# main.net
KiCad netlist of a schematic drawn in EAGLE
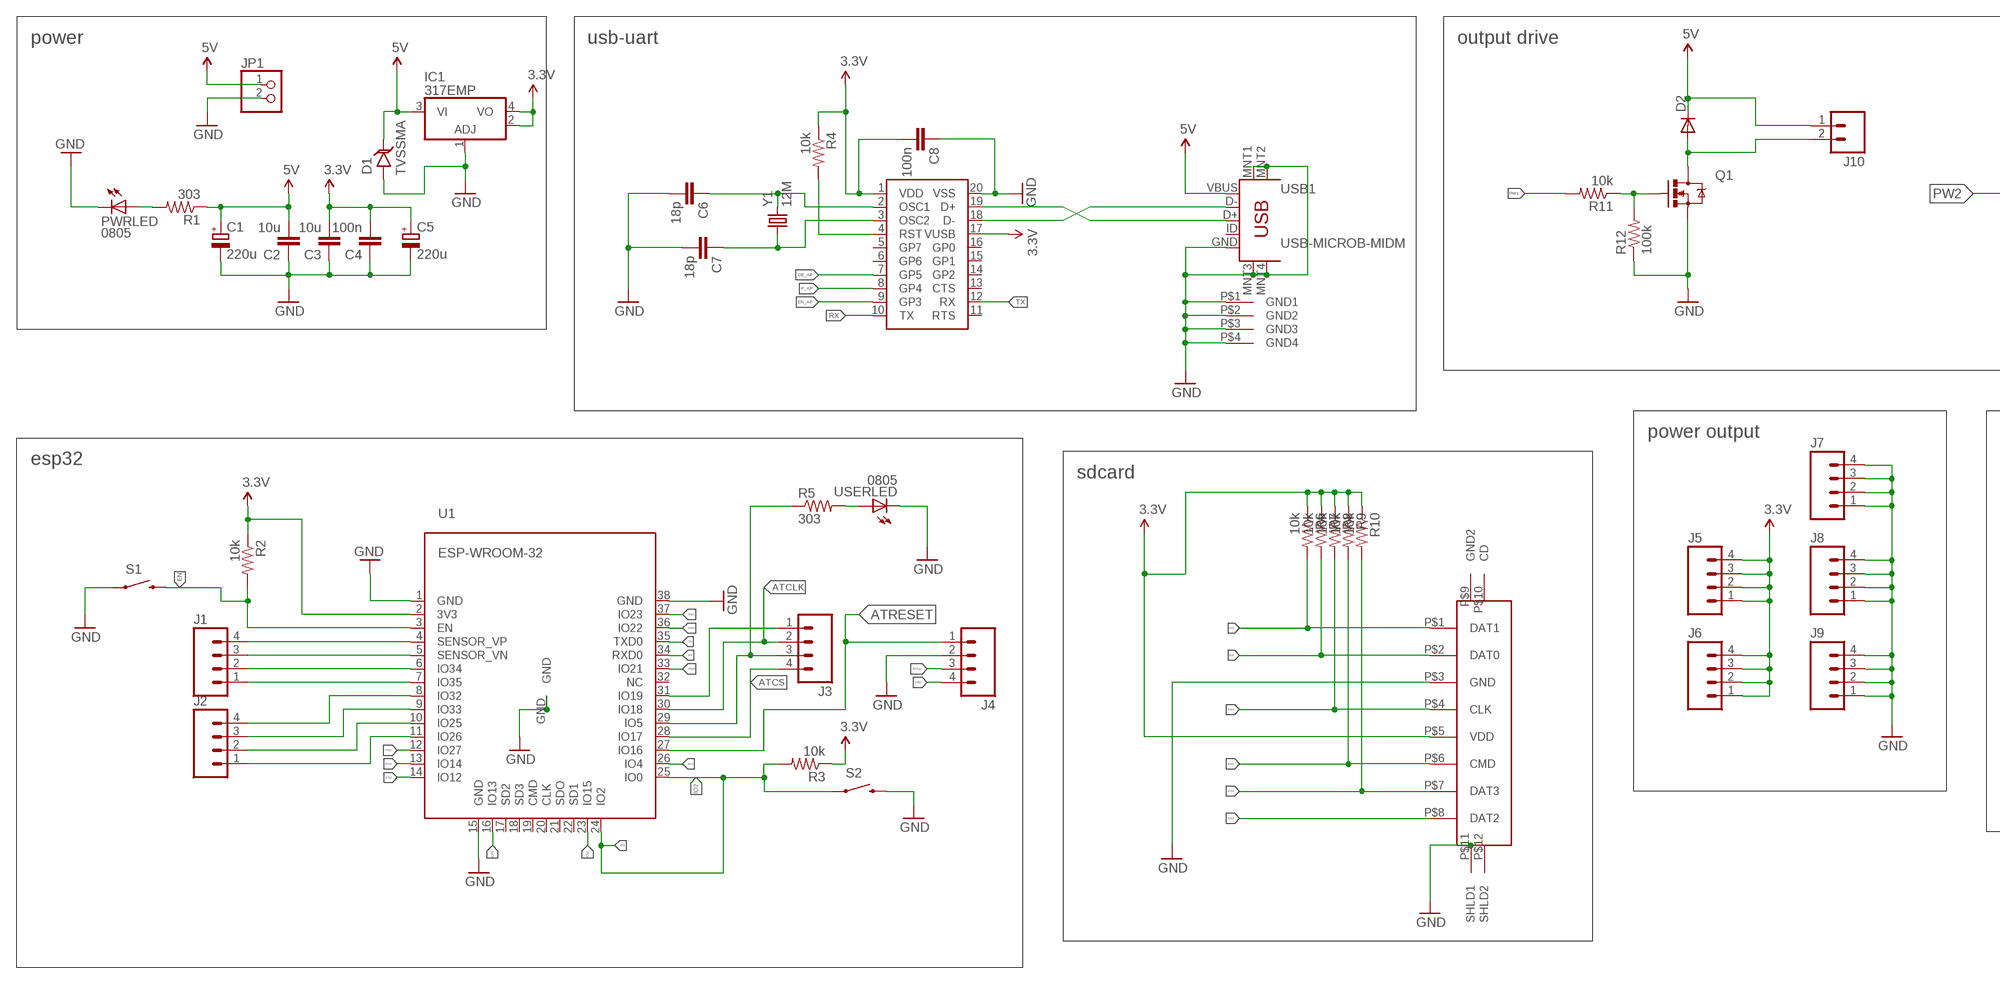
[diagram p0: schematic, sheet 1, part 1 of 2]
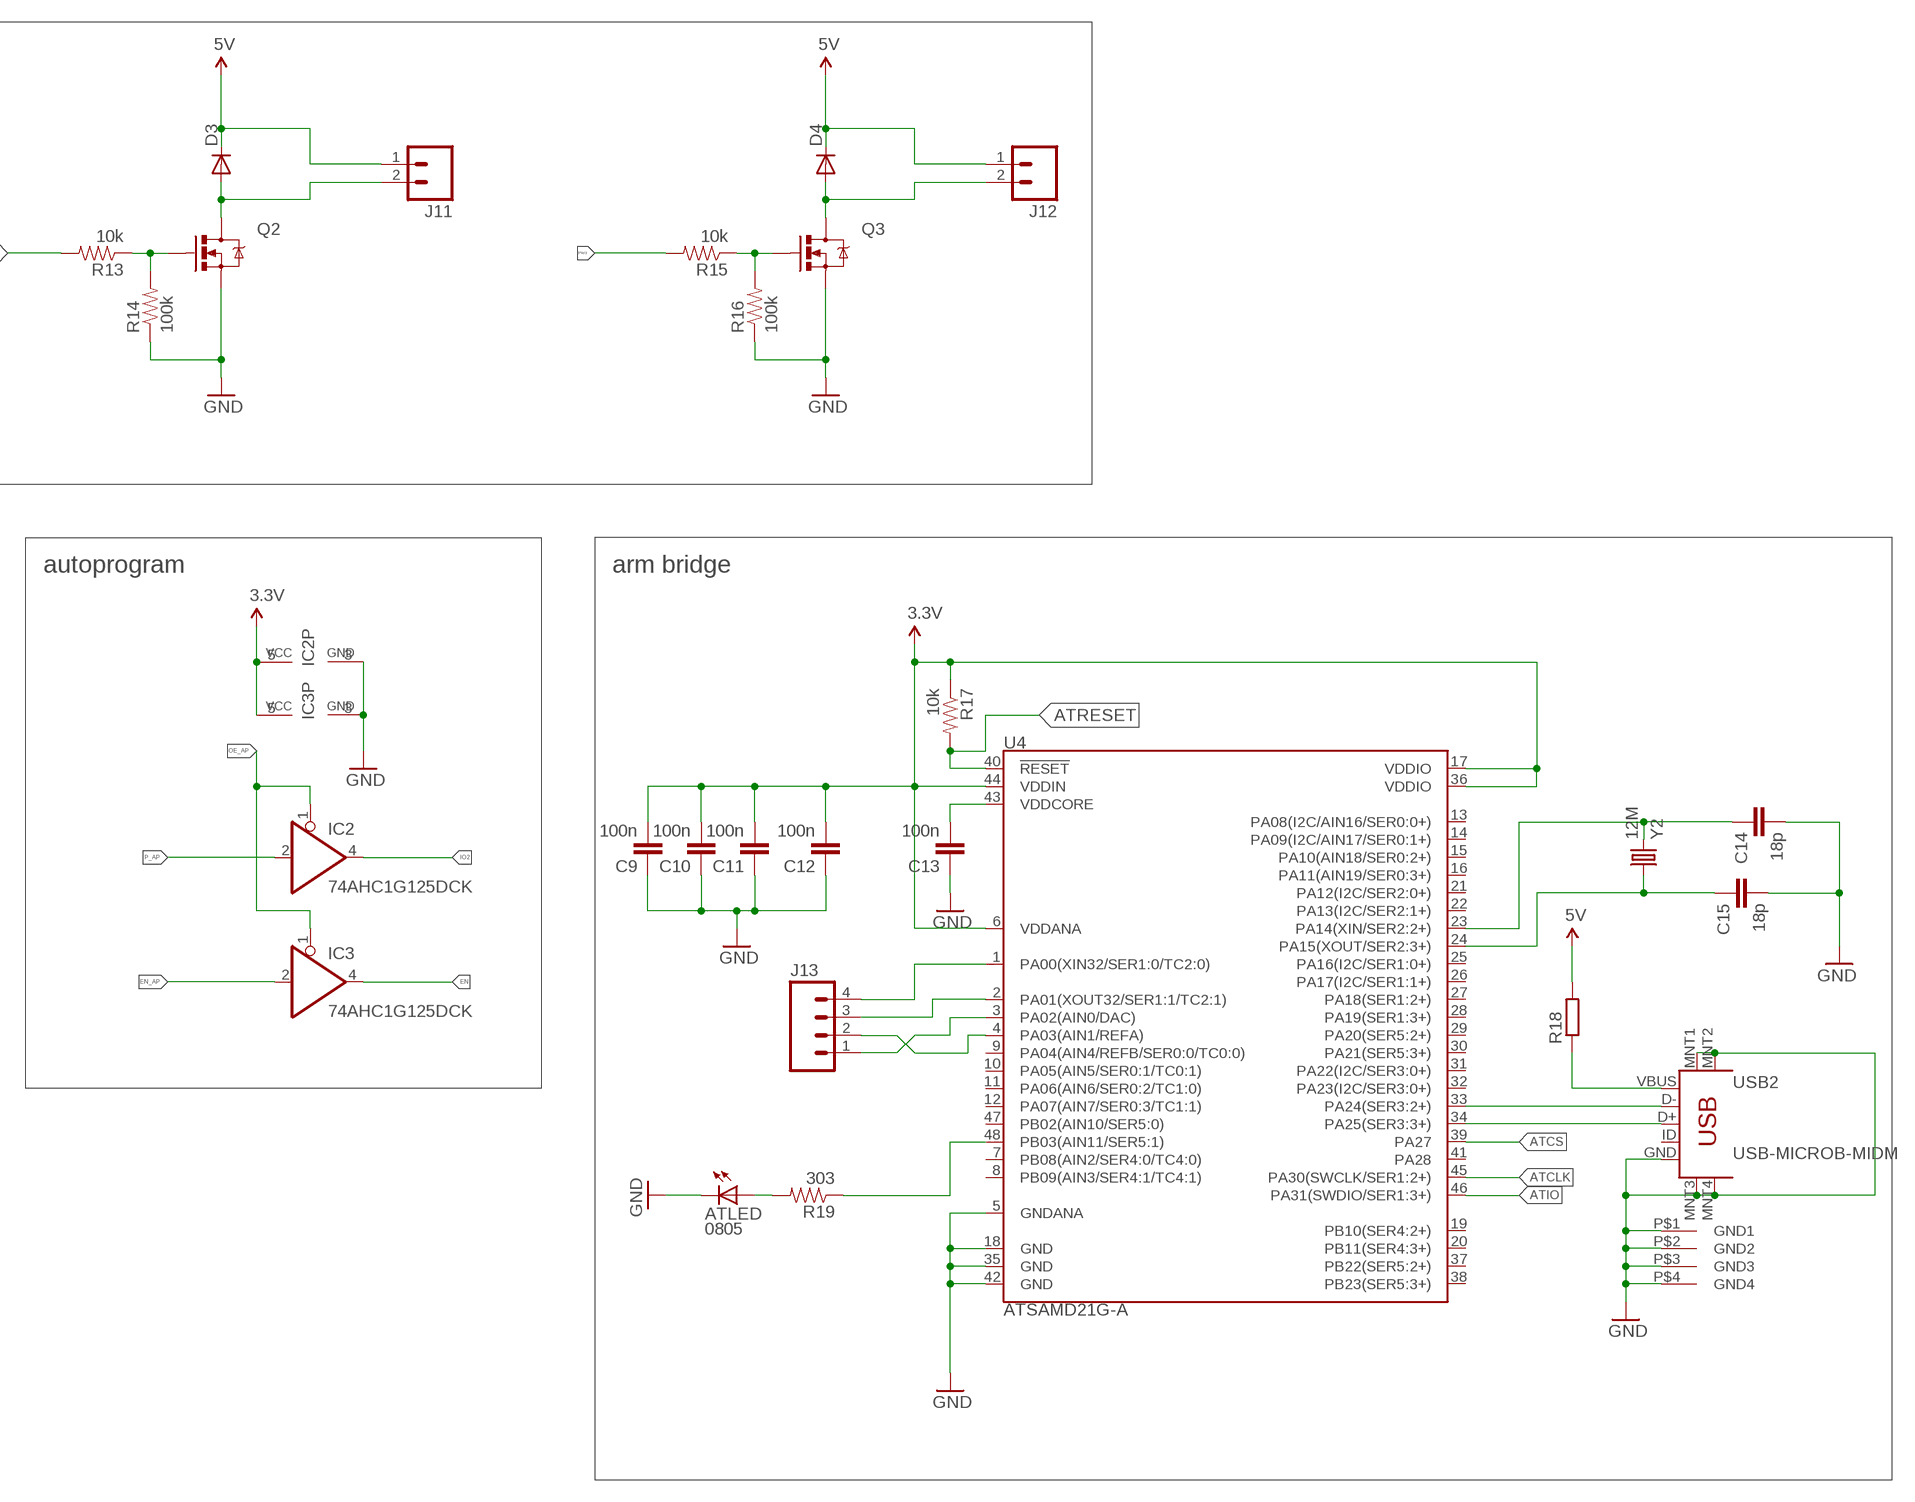
[diagram p1: schematic, sheet 1, part 2 of 2]

(export (version "E")
  (design (tool "Eeschema 10.0.6"))
  (components
    (comp (ref "ATLED")
      (value "0805")
      (footprint "eagle-import:SML0805")
      (libsource (lib "eagle-import") (part "LEDSML0805"))
    )
    (comp (ref "C1")
      (value "220u")
      (footprint "eagle-import:E2-4")
      (libsource (lib "eagle-import") (part "CPOL-EUE2-4"))
    )
    (comp (ref "C2")
      (value "10u")
      (footprint "eagle-import:0805")
      (libsource (lib "eagle-import") (part "CAP0805"))
    )
    (comp (ref "C3")
      (value "10u")
      (footprint "eagle-import:0805")
      (libsource (lib "eagle-import") (part "CAP0805"))
    )
    (comp (ref "C4")
      (value "100n")
      (footprint "eagle-import:0603-CAP")
      (libsource (lib "eagle-import") (part "CAP0603-CAP"))
    )
    (comp (ref "C5")
      (value "220u")
      (footprint "eagle-import:E2-4")
      (libsource (lib "eagle-import") (part "CPOL-EUE2-4"))
    )
    (comp (ref "C6")
      (value "18p")
      (footprint "eagle-import:0603-CAP")
      (libsource (lib "eagle-import") (part "CAP0603-CAP"))
    )
    (comp (ref "C7")
      (value "18p")
      (footprint "eagle-import:0603-CAP")
      (libsource (lib "eagle-import") (part "CAP0603-CAP"))
    )
    (comp (ref "C8")
      (value "100n")
      (footprint "eagle-import:0603-CAP")
      (libsource (lib "eagle-import") (part "CAP0603-CAP"))
    )
    (comp (ref "C9")
      (value "100n")
      (footprint "eagle-import:C0603K")
      (libsource (lib "eagle-import") (part "C-EUC0603K"))
    )
    (comp (ref "C10")
      (value "100n")
      (footprint "eagle-import:C0603K")
      (libsource (lib "eagle-import") (part "C-EUC0603K"))
    )
    (comp (ref "C11")
      (value "100n")
      (footprint "eagle-import:C0603K")
      (libsource (lib "eagle-import") (part "C-EUC0603K"))
    )
    (comp (ref "C12")
      (value "100n")
      (footprint "eagle-import:C0603K")
      (libsource (lib "eagle-import") (part "C-EUC0603K"))
    )
    (comp (ref "C13")
      (value "100n")
      (footprint "eagle-import:C0603K")
      (libsource (lib "eagle-import") (part "C-EUC0603K"))
    )
    (comp (ref "C14")
      (value "18p")
      (footprint "eagle-import:0603-CAP")
      (libsource (lib "eagle-import") (part "CAP0603-CAP"))
    )
    (comp (ref "C15")
      (value "18p")
      (footprint "eagle-import:0603-CAP")
      (libsource (lib "eagle-import") (part "CAP0603-CAP"))
    )
    (comp (ref "D1")
      (value "TVSSMA")
      (footprint "eagle-import:SMA-DIODE")
      (libsource (lib "eagle-import") (part "TVSSMA"))
    )
    (comp (ref "D2")
      (value "DIODE-SOD323-W")
      (footprint "eagle-import:SOD323-W")
      (libsource (lib "eagle-import") (part "DIODE-SOD323-W"))
    )
    (comp (ref "D3")
      (value "DIODE-SOD323-W")
      (footprint "eagle-import:SOD323-W")
      (libsource (lib "eagle-import") (part "DIODE-SOD323-W"))
    )
    (comp (ref "D4")
      (value "DIODE-SOD323-W")
      (footprint "eagle-import:SOD323-W")
      (libsource (lib "eagle-import") (part "DIODE-SOD323-W"))
    )
    (comp (ref "IC1")
      (value "317EMP")
      (footprint "eagle-import:SOT223")
      (libsource (lib "eagle-import") (part "317EMP"))
    )
    (comp (ref "IC2")
      (value "74AHC1G125DCK")
      (footprint "eagle-import:SC70-5")
      (libsource (lib "eagle-import") (part "741G125DCKAHC"))
    )
    (comp (ref "IC3")
      (value "74AHC1G125DCK")
      (footprint "eagle-import:SC70-5")
      (libsource (lib "eagle-import") (part "741G125DCKAHC"))
    )
    (comp (ref "J1")
      (value "M04LONGPADS")
      (footprint "eagle-import:1X04_LONGPADS")
      (libsource (lib "eagle-import") (part "M04LONGPADS"))
    )
    (comp (ref "J2")
      (value "M04LONGPADS")
      (footprint "eagle-import:1X04_LONGPADS")
      (libsource (lib "eagle-import") (part "M04LONGPADS"))
    )
    (comp (ref "J3")
      (value "M041.27MM")
      (footprint "eagle-import:1X04-1.27MM")
      (libsource (lib "eagle-import") (part "M041.27MM"))
    )
    (comp (ref "J4")
      (value "M041.27MM")
      (footprint "eagle-import:1X04-1.27MM")
      (libsource (lib "eagle-import") (part "M041.27MM"))
    )
    (comp (ref "J5")
      (value "M04LONGPADS")
      (footprint "eagle-import:1X04_LONGPADS")
      (libsource (lib "eagle-import") (part "M04LONGPADS"))
    )
    (comp (ref "J6")
      (value "M04LONGPADS")
      (footprint "eagle-import:1X04_LONGPADS")
      (libsource (lib "eagle-import") (part "M04LONGPADS"))
    )
    (comp (ref "J7")
      (value "M04LONGPADS")
      (footprint "eagle-import:1X04_LONGPADS")
      (libsource (lib "eagle-import") (part "M04LONGPADS"))
    )
    (comp (ref "J8")
      (value "M04LONGPADS")
      (footprint "eagle-import:1X04_LONGPADS")
      (libsource (lib "eagle-import") (part "M04LONGPADS"))
    )
    (comp (ref "J9")
      (value "M04LONGPADS")
      (footprint "eagle-import:1X04_LONGPADS")
      (libsource (lib "eagle-import") (part "M04LONGPADS"))
    )
    (comp (ref "J10")
      (value "M02LOCK_LONGPADS")
      (footprint "eagle-import:1X02_LOCK_LONGPADS")
      (libsource (lib "eagle-import") (part "M02LOCK_LONGPADS"))
    )
    (comp (ref "J11")
      (value "M02LOCK_LONGPADS")
      (footprint "eagle-import:1X02_LOCK_LONGPADS")
      (libsource (lib "eagle-import") (part "M02LOCK_LONGPADS"))
    )
    (comp (ref "J12")
      (value "M02LOCK_LONGPADS")
      (footprint "eagle-import:1X02_LOCK_LONGPADS")
      (libsource (lib "eagle-import") (part "M02LOCK_LONGPADS"))
    )
    (comp (ref "J13")
      (value "M041.27MM")
      (footprint "eagle-import:1X04-1.27MM")
      (libsource (lib "eagle-import") (part "M041.27MM"))
    )
    (comp (ref "JP1")
      (value "PINHD-1X2")
      (footprint "eagle-import:1X02")
      (libsource (lib "eagle-import") (part "PINHD-1X2"))
    )
    (comp (ref "PWRLED")
      (value "0805")
      (footprint "eagle-import:SML0805")
      (libsource (lib "eagle-import") (part "LEDSML0805"))
    )
    (comp (ref "Q1")
      (value "MOSFET-NCHANNELBSS138")
      (footprint "eagle-import:SOT23-3")
      (libsource (lib "eagle-import") (part "MOSFET-NCHANNELBSS138"))
    )
    (comp (ref "Q2")
      (value "MOSFET-NCHANNELBSS138")
      (footprint "eagle-import:SOT23-3")
      (libsource (lib "eagle-import") (part "MOSFET-NCHANNELBSS138"))
    )
    (comp (ref "Q3")
      (value "MOSFET-NCHANNELBSS138")
      (footprint "eagle-import:SOT23-3")
      (libsource (lib "eagle-import") (part "MOSFET-NCHANNELBSS138"))
    )
    (comp (ref "R1")
      (value "303")
      (footprint "eagle-import:0805")
      (libsource (lib "eagle-import") (part "RESISTOR0805-RES"))
    )
    (comp (ref "R2")
      (value "10k")
      (footprint "eagle-import:0805")
      (libsource (lib "eagle-import") (part "RESISTOR0805-RES"))
    )
    (comp (ref "R3")
      (value "10k")
      (footprint "eagle-import:0805")
      (libsource (lib "eagle-import") (part "RESISTOR0805-RES"))
    )
    (comp (ref "R4")
      (value "10k")
      (footprint "eagle-import:0805")
      (libsource (lib "eagle-import") (part "RESISTOR0805-RES"))
    )
    (comp (ref "R5")
      (value "303")
      (footprint "eagle-import:0805")
      (libsource (lib "eagle-import") (part "RESISTOR0805-RES"))
    )
    (comp (ref "R6")
      (value "10k")
      (footprint "eagle-import:0805")
      (libsource (lib "eagle-import") (part "RESISTOR0805-RES"))
    )
    (comp (ref "R7")
      (value "10k")
      (footprint "eagle-import:0805")
      (libsource (lib "eagle-import") (part "RESISTOR0805-RES"))
    )
    (comp (ref "R8")
      (value "10k")
      (footprint "eagle-import:0805")
      (libsource (lib "eagle-import") (part "RESISTOR0805-RES"))
    )
    (comp (ref "R9")
      (value "10k")
      (footprint "eagle-import:0805")
      (libsource (lib "eagle-import") (part "RESISTOR0805-RES"))
    )
    (comp (ref "R10")
      (value "10k")
      (footprint "eagle-import:0805")
      (libsource (lib "eagle-import") (part "RESISTOR0805-RES"))
    )
    (comp (ref "R11")
      (value "10k")
      (footprint "eagle-import:0805")
      (libsource (lib "eagle-import") (part "RESISTOR0805-RES"))
    )
    (comp (ref "R12")
      (value "100k")
      (footprint "eagle-import:0805")
      (libsource (lib "eagle-import") (part "RESISTOR0805-RES"))
    )
    (comp (ref "R13")
      (value "10k")
      (footprint "eagle-import:0805")
      (libsource (lib "eagle-import") (part "RESISTOR0805-RES"))
    )
    (comp (ref "R14")
      (value "100k")
      (footprint "eagle-import:0805")
      (libsource (lib "eagle-import") (part "RESISTOR0805-RES"))
    )
    (comp (ref "R15")
      (value "10k")
      (footprint "eagle-import:0805")
      (libsource (lib "eagle-import") (part "RESISTOR0805-RES"))
    )
    (comp (ref "R16")
      (value "100k")
      (footprint "eagle-import:0805")
      (libsource (lib "eagle-import") (part "RESISTOR0805-RES"))
    )
    (comp (ref "R17")
      (value "10k")
      (footprint "eagle-import:0805")
      (libsource (lib "eagle-import") (part "RESISTOR0805-RES"))
    )
    (comp (ref "R18")
      (value "R-EU_R2010W")
      (footprint "eagle-import:R2010W")
      (libsource (lib "eagle-import") (part "R-EU_R2010W"))
    )
    (comp (ref "R19")
      (value "303")
      (footprint "eagle-import:0805")
      (libsource (lib "eagle-import") (part "RESISTOR0805-RES"))
    )
    (comp (ref "S1")
      (value "SWITCH-MOMENTARY-2SMD")
      (footprint "eagle-import:TACTILE-SWITCH-SMD")
      (libsource (lib "eagle-import") (part "SWITCH-MOMENTARY-2SMD"))
    )
    (comp (ref "S2")
      (value "SWITCH-MOMENTARY-2SMD")
      (footprint "eagle-import:TACTILE-SWITCH-SMD")
      (libsource (lib "eagle-import") (part "SWITCH-MOMENTARY-2SMD"))
    )
    (comp (ref "U1")
      (value "ESP-WROOM-32")
      (footprint "eagle-import:ESP-WROOM-32")
      (libsource (lib "eagle-import") (part "ESP-WROOM-32"))
    )
    (comp (ref "U2")
      (value "MCP2200")
      (footprint "eagle-import:SO20W")
      (libsource (lib "eagle-import") (part "MCP2200"))
    )
    (comp (ref "U3")
      (value "MICROSD")
      (footprint "eagle-import:MICROSD")
      (libsource (lib "eagle-import") (part "MICROSD"))
    )
    (comp (ref "U4")
      (value "ATSAMD21G-A")
      (footprint "eagle-import:TQFP-48")
      (libsource (lib "eagle-import") (part "ATSAMD21G-A"))
    )
    (comp (ref "USB1")
      (value "USB-MICROB-MIDM")
      (footprint "eagle-import:USB-B-MICRO-MIDM")
      (libsource (lib "eagle-import") (part "USB-MICROB-MIDM"))
    )
    (comp (ref "USB2")
      (value "USB-MICROB-MIDM")
      (footprint "eagle-import:USB-B-MICRO-MIDM")
      (libsource (lib "eagle-import") (part "USB-MICROB-MIDM"))
    )
    (comp (ref "USERLED")
      (value "0805")
      (footprint "eagle-import:SML0805")
      (libsource (lib "eagle-import") (part "LEDSML0805"))
    )
    (comp (ref "Y1")
      (value "12M")
      (footprint "eagle-import:CRYSTAL-TXC-7A")
      (libsource (lib "eagle-import") (part "CRYSTALTXC-7A"))
    )
    (comp (ref "Y2")
      (value "12M")
      (footprint "eagle-import:CRYSTAL-TXC-7A")
      (libsource (lib "eagle-import") (part "CRYSTALTXC-7A"))
    )
  )
  (nets
    (net (code "1") (name "3.3V") (class "Default")
      (node (ref "C10") (pin "2") (pinfunction "2_2") (pintype "passive"))
      (node (ref "C11") (pin "2") (pinfunction "2_2") (pintype "passive"))
      (node (ref "C12") (pin "2") (pinfunction "2_2") (pintype "passive"))
      (node (ref "C3") (pin "2") (pinfunction "2_2") (pintype "passive"))
      (node (ref "C4") (pin "2") (pinfunction "2_2") (pintype "passive"))
      (node (ref "C5") (pin "+") (pinfunction "+_+") (pintype "passive"))
      (node (ref "C8") (pin "2") (pinfunction "2_2") (pintype "passive"))
      (node (ref "C9") (pin "2") (pinfunction "2_2") (pintype "passive"))
      (node (ref "IC1") (pin "2") (pinfunction "VO2_2") (pintype "passive"))
      (node (ref "IC1") (pin "4") (pinfunction "VO_4") (pintype "passive"))
      (node (ref "IC2") (pin "5") (pinfunction "VCC_5") (pintype "power_in"))
      (node (ref "IC3") (pin "5") (pinfunction "VCC_5") (pintype "power_in"))
      (node (ref "J5") (pin "1") (pinfunction "1_1") (pintype "passive"))
      (node (ref "J5") (pin "2") (pinfunction "2_2") (pintype "passive"))
      (node (ref "J5") (pin "3") (pinfunction "3_3") (pintype "passive"))
      (node (ref "J5") (pin "4") (pinfunction "4_4") (pintype "passive"))
      (node (ref "J6") (pin "1") (pinfunction "1_1") (pintype "passive"))
      (node (ref "J6") (pin "2") (pinfunction "2_2") (pintype "passive"))
      (node (ref "J6") (pin "3") (pinfunction "3_3") (pintype "passive"))
      (node (ref "J6") (pin "4") (pinfunction "4_4") (pintype "passive"))
      (node (ref "R10") (pin "1") (pinfunction "1_1") (pintype "passive"))
      (node (ref "R17") (pin "1") (pinfunction "1_1") (pintype "passive"))
      (node (ref "R2") (pin "1") (pinfunction "1_1") (pintype "passive"))
      (node (ref "R3") (pin "1") (pinfunction "1_1") (pintype "passive"))
      (node (ref "R4") (pin "1") (pinfunction "1_1") (pintype "passive"))
      (node (ref "R6") (pin "1") (pinfunction "1_1") (pintype "passive"))
      (node (ref "R7") (pin "1") (pinfunction "1_1") (pintype "passive"))
      (node (ref "R8") (pin "1") (pinfunction "1_1") (pintype "passive"))
      (node (ref "R9") (pin "1") (pinfunction "1_1") (pintype "passive"))
      (node (ref "U1") (pin "2") (pinfunction "3V3_2") (pintype "bidirectional"))
      (node (ref "U2") (pin "1") (pinfunction "VDD_1") (pintype "bidirectional"))
      (node (ref "U2") (pin "17") (pinfunction "VUSB_17") (pintype "bidirectional"))
      (node (ref "U3") (pin "P$5") (pinfunction "VDD_P$5") (pintype "bidirectional"))
      (node (ref "U4") (pin "17") (pinfunction "VDDIO_17") (pintype "bidirectional"))
      (node (ref "U4") (pin "36") (pinfunction "VDDIO_36") (pintype "bidirectional"))
      (node (ref "U4") (pin "44") (pinfunction "VDDIN_44") (pintype "bidirectional"))
      (node (ref "U4") (pin "6") (pinfunction "VDDANA_6") (pintype "bidirectional"))
    )
    (net (code "2") (name "5V") (class "Default")
      (node (ref "C1") (pin "+") (pinfunction "+_+") (pintype "passive"))
      (node (ref "C2") (pin "2") (pinfunction "2_2") (pintype "passive"))
      (node (ref "D1") (pin "C") (pinfunction "C_C") (pintype "passive"))
      (node (ref "D2") (pin "C") (pinfunction "C_C") (pintype "passive"))
      (node (ref "D3") (pin "C") (pinfunction "C_C") (pintype "passive"))
      (node (ref "D4") (pin "C") (pinfunction "C_C") (pintype "passive"))
      (node (ref "IC1") (pin "3") (pinfunction "VI_3") (pintype "input"))
      (node (ref "J10") (pin "1") (pinfunction "1_1") (pintype "passive"))
      (node (ref "J11") (pin "1") (pinfunction "1_1") (pintype "passive"))
      (node (ref "J12") (pin "1") (pinfunction "1_1") (pintype "passive"))
      (node (ref "JP1") (pin "1") (pinfunction "1_1") (pintype "passive"))
      (node (ref "R1") (pin "1") (pinfunction "1_1") (pintype "passive"))
      (node (ref "R18") (pin "2") (pinfunction "2_2") (pintype "passive"))
      (node (ref "USB1") (pin "VBUS") (pinfunction "VBUS_VBUS") (pintype "bidirectional"))
    )
    (net (code "3") (name "ATCLK") (class "Default")
      (node (ref "J3") (pin "2") (pinfunction "2_2") (pintype "passive"))
      (node (ref "J4") (pin "3") (pinfunction "3_3") (pintype "passive"))
      (node (ref "U1") (pin "30") (pinfunction "IO18_30") (pintype "bidirectional"))
      (node (ref "U4") (pin "45") (pinfunction "PA30(SWCLK/SER1:2+)_45") (pintype "bidirectional"))
    )
    (net (code "4") (name "ATCS") (class "Default")
      (node (ref "J3") (pin "4") (pinfunction "4_4") (pintype "passive"))
      (node (ref "U1") (pin "28") (pinfunction "IO17_28") (pintype "bidirectional"))
      (node (ref "U4") (pin "39") (pinfunction "PA27_39") (pintype "bidirectional"))
    )
    (net (code "5") (name "ATIO") (class "Default")
      (node (ref "J4") (pin "4") (pinfunction "4_4") (pintype "passive"))
      (node (ref "U1") (pin "12") (pinfunction "IO27_12") (pintype "bidirectional"))
      (node (ref "U4") (pin "46") (pinfunction "PA31(SWDIO/SER1:3+)_46") (pintype "bidirectional"))
    )
    (net (code "6") (name "ATRESET") (class "Default")
      (node (ref "J4") (pin "1") (pinfunction "1_1") (pintype "passive"))
      (node (ref "R17") (pin "2") (pinfunction "2_2") (pintype "passive"))
      (node (ref "U1") (pin "27") (pinfunction "IO16_27") (pintype "bidirectional"))
      (node (ref "U4") (pin "40") (pinfunction "~{RESET}_40") (pintype "bidirectional"))
    )
    (net (code "7") (name "EN") (class "Default")
      (node (ref "IC3") (pin "4") (pinfunction "O_4") (pintype "tri_state"))
      (node (ref "R2") (pin "2") (pinfunction "2_2") (pintype "passive"))
      (node (ref "S1") (pin "3") (pinfunction "2_3") (pintype "passive"))
      (node (ref "U1") (pin "3") (pinfunction "EN_3") (pintype "bidirectional"))
    )
    (net (code "8") (name "EN_AP") (class "Default")
      (node (ref "IC3") (pin "2") (pinfunction "I_2") (pintype "input"))
      (node (ref "U2") (pin "9") (pinfunction "GP3_9") (pintype "bidirectional"))
    )
    (net (code "9") (name "GND") (class "Default")
      (node (ref "ATLED") (pin "C") (pinfunction "C_C") (pintype "passive"))
      (node (ref "C1") (pin "-") (pinfunction "-_-") (pintype "passive"))
      (node (ref "C10") (pin "1") (pinfunction "1_1") (pintype "passive"))
      (node (ref "C11") (pin "1") (pinfunction "1_1") (pintype "passive"))
      (node (ref "C12") (pin "1") (pinfunction "1_1") (pintype "passive"))
      (node (ref "C13") (pin "1") (pinfunction "1_1") (pintype "passive"))
      (node (ref "C14") (pin "2") (pinfunction "2_2") (pintype "passive"))
      (node (ref "C15") (pin "2") (pinfunction "2_2") (pintype "passive"))
      (node (ref "C2") (pin "1") (pinfunction "1_1") (pintype "passive"))
      (node (ref "C3") (pin "1") (pinfunction "1_1") (pintype "passive"))
      (node (ref "C4") (pin "1") (pinfunction "1_1") (pintype "passive"))
      (node (ref "C5") (pin "-") (pinfunction "-_-") (pintype "passive"))
      (node (ref "C6") (pin "2") (pinfunction "2_2") (pintype "passive"))
      (node (ref "C7") (pin "2") (pinfunction "2_2") (pintype "passive"))
      (node (ref "C8") (pin "1") (pinfunction "1_1") (pintype "passive"))
      (node (ref "C9") (pin "1") (pinfunction "1_1") (pintype "passive"))
      (node (ref "D1") (pin "A") (pinfunction "A_A") (pintype "passive"))
      (node (ref "IC1") (pin "1") (pinfunction "ADJ_1") (pintype "input"))
      (node (ref "IC2") (pin "3") (pinfunction "GND_3") (pintype "power_in"))
      (node (ref "IC3") (pin "3") (pinfunction "GND_3") (pintype "power_in"))
      (node (ref "J4") (pin "2") (pinfunction "2_2") (pintype "passive"))
      (node (ref "J7") (pin "1") (pinfunction "1_1") (pintype "passive"))
      (node (ref "J7") (pin "2") (pinfunction "2_2") (pintype "passive"))
      (node (ref "J7") (pin "3") (pinfunction "3_3") (pintype "passive"))
      (node (ref "J7") (pin "4") (pinfunction "4_4") (pintype "passive"))
      (node (ref "J8") (pin "1") (pinfunction "1_1") (pintype "passive"))
      (node (ref "J8") (pin "2") (pinfunction "2_2") (pintype "passive"))
      (node (ref "J8") (pin "3") (pinfunction "3_3") (pintype "passive"))
      (node (ref "J8") (pin "4") (pinfunction "4_4") (pintype "passive"))
      (node (ref "J9") (pin "1") (pinfunction "1_1") (pintype "passive"))
      (node (ref "J9") (pin "2") (pinfunction "2_2") (pintype "passive"))
      (node (ref "J9") (pin "3") (pinfunction "3_3") (pintype "passive"))
      (node (ref "J9") (pin "4") (pinfunction "4_4") (pintype "passive"))
      (node (ref "JP1") (pin "2") (pinfunction "2_2") (pintype "passive"))
      (node (ref "PWRLED") (pin "C") (pinfunction "C_C") (pintype "passive"))
      (node (ref "Q1") (pin "2") (pinfunction "S_2") (pintype "passive"))
      (node (ref "Q2") (pin "2") (pinfunction "S_2") (pintype "passive"))
      (node (ref "Q3") (pin "2") (pinfunction "S_2") (pintype "passive"))
      (node (ref "R12") (pin "1") (pinfunction "1_1") (pintype "passive"))
      (node (ref "R14") (pin "1") (pinfunction "1_1") (pintype "passive"))
      (node (ref "R16") (pin "1") (pinfunction "1_1") (pintype "passive"))
      (node (ref "S1") (pin "1") (pinfunction "1_1") (pintype "passive"))
      (node (ref "S2") (pin "3") (pinfunction "2_3") (pintype "passive"))
      (node (ref "U1") (pin "1") (pinfunction "GND_1") (pintype "bidirectional"))
      (node (ref "U1") (pin "15") (pinfunction "GND_15") (pintype "bidirectional"))
      (node (ref "U1") (pin "38") (pinfunction "GND_38") (pintype "bidirectional"))
      (node (ref "U1") (pin "GND") (pinfunction "GND_GND") (pintype "bidirectional"))
      (node (ref "U2") (pin "20") (pinfunction "VSS_20") (pintype "bidirectional"))
      (node (ref "U3") (pin "P$11") (pinfunction "SHLD1_P$11") (pintype "bidirectional"))
      (node (ref "U3") (pin "P$12") (pinfunction "SHLD2_P$12") (pintype "bidirectional"))
      (node (ref "U3") (pin "P$3") (pinfunction "GND_P$3") (pintype "bidirectional"))
      (node (ref "U4") (pin "18") (pinfunction "GND_18") (pintype "bidirectional"))
      (node (ref "U4") (pin "35") (pinfunction "GND_35") (pintype "bidirectional"))
      (node (ref "U4") (pin "42") (pinfunction "GND_42") (pintype "bidirectional"))
      (node (ref "U4") (pin "5") (pinfunction "GNDANA_5") (pintype "bidirectional"))
      (node (ref "USB1") (pin "GND") (pinfunction "GND_GND") (pintype "bidirectional"))
      (node (ref "USB1") (pin "MNT1") (pinfunction "MTN1_MNT1") (pintype "bidirectional"))
      (node (ref "USB1") (pin "MNT2") (pinfunction "MTN2_MNT2") (pintype "bidirectional"))
      (node (ref "USB1") (pin "MNT3") (pinfunction "MTN3_MNT3") (pintype "bidirectional"))
      (node (ref "USB1") (pin "MNT4") (pinfunction "MTN4_MNT4") (pintype "bidirectional"))
      (node (ref "USB1") (pin "P$1") (pinfunction "GND1_P$1") (pintype "bidirectional"))
      (node (ref "USB1") (pin "P$2") (pinfunction "GND2_P$2") (pintype "bidirectional"))
      (node (ref "USB1") (pin "P$3") (pinfunction "GND3_P$3") (pintype "bidirectional"))
      (node (ref "USB1") (pin "P$4") (pinfunction "GND4_P$4") (pintype "bidirectional"))
      (node (ref "USB2") (pin "GND") (pinfunction "GND_GND") (pintype "bidirectional"))
      (node (ref "USB2") (pin "MNT1") (pinfunction "MTN1_MNT1") (pintype "bidirectional"))
      (node (ref "USB2") (pin "MNT2") (pinfunction "MTN2_MNT2") (pintype "bidirectional"))
      (node (ref "USB2") (pin "MNT3") (pinfunction "MTN3_MNT3") (pintype "bidirectional"))
      (node (ref "USB2") (pin "MNT4") (pinfunction "MTN4_MNT4") (pintype "bidirectional"))
      (node (ref "USB2") (pin "P$1") (pinfunction "GND1_P$1") (pintype "bidirectional"))
      (node (ref "USB2") (pin "P$2") (pinfunction "GND2_P$2") (pintype "bidirectional"))
      (node (ref "USB2") (pin "P$3") (pinfunction "GND3_P$3") (pintype "bidirectional"))
      (node (ref "USB2") (pin "P$4") (pinfunction "GND4_P$4") (pintype "bidirectional"))
      (node (ref "USERLED") (pin "C") (pinfunction "C_C") (pintype "passive"))
    )
    (net (code "10") (name "IO2") (class "Default")
      (node (ref "IC2") (pin "4") (pinfunction "O_4") (pintype "tri_state"))
      (node (ref "R3") (pin "2") (pinfunction "2_2") (pintype "passive"))
      (node (ref "R7") (pin "2") (pinfunction "2_2") (pintype "passive"))
      (node (ref "S2") (pin "1") (pinfunction "1_1") (pintype "passive"))
      (node (ref "U1") (pin "24") (pinfunction "IO2_24") (pintype "bidirectional"))
      (node (ref "U1") (pin "25") (pinfunction "IO0_25") (pintype "bidirectional"))
      (node (ref "U3") (pin "P$2") (pinfunction "DAT0_P$2") (pintype "bidirectional"))
    )
    (net (code "11") (name "IO4") (class "Default")
      (node (ref "R6") (pin "2") (pinfunction "2_2") (pintype "passive"))
      (node (ref "U1") (pin "26") (pinfunction "IO4_26") (pintype "bidirectional"))
      (node (ref "U3") (pin "P$1") (pinfunction "DAT1_P$1") (pintype "bidirectional"))
    )
    (net (code "12") (name "IO12") (class "Default")
      (node (ref "U1") (pin "14") (pinfunction "IO12_14") (pintype "bidirectional"))
      (node (ref "U3") (pin "P$8") (pinfunction "DAT2_P$8") (pintype "bidirectional"))
    )
    (net (code "13") (name "IO13") (class "Default")
      (node (ref "R10") (pin "2") (pinfunction "2_2") (pintype "passive"))
      (node (ref "U1") (pin "16") (pinfunction "IO13_16") (pintype "bidirectional"))
      (node (ref "U3") (pin "P$7") (pinfunction "DAT3_P$7") (pintype "bidirectional"))
    )
    (net (code "14") (name "IO14") (class "Default")
      (node (ref "R8") (pin "2") (pinfunction "2_2") (pintype "passive"))
      (node (ref "U1") (pin "13") (pinfunction "IO14_13") (pintype "bidirectional"))
      (node (ref "U3") (pin "P$4") (pinfunction "CLK_P$4") (pintype "bidirectional"))
    )
    (net (code "15") (name "IO15") (class "Default")
      (node (ref "R9") (pin "2") (pinfunction "2_2") (pintype "passive"))
      (node (ref "U1") (pin "23") (pinfunction "IO15_23") (pintype "bidirectional"))
      (node (ref "U3") (pin "P$6") (pinfunction "CMD_P$6") (pintype "bidirectional"))
    )
    (net (code "16") (name "Net-(ATLED-PadA)") (class "Default")
      (node (ref "ATLED") (pin "A") (pinfunction "A_A") (pintype "passive"))
      (node (ref "R19") (pin "2") (pinfunction "2_2") (pintype "passive"))
    )
    (net (code "17") (name "Net-(PWRLED-PadA)") (class "Default")
      (node (ref "PWRLED") (pin "A") (pinfunction "A_A") (pintype "passive"))
      (node (ref "R1") (pin "2") (pinfunction "2_2") (pintype "passive"))
    )
    (net (code "18") (name "Net-(Q1-D)") (class "Default")
      (node (ref "D2") (pin "A") (pinfunction "A_A") (pintype "passive"))
      (node (ref "J10") (pin "2") (pinfunction "2_2") (pintype "passive"))
      (node (ref "Q1") (pin "3") (pinfunction "D_3") (pintype "passive"))
    )
    (net (code "19") (name "Net-(Q1-G)") (class "Default")
      (node (ref "Q1") (pin "1") (pinfunction "G_1") (pintype "passive"))
      (node (ref "R11") (pin "1") (pinfunction "1_1") (pintype "passive"))
      (node (ref "R12") (pin "2") (pinfunction "2_2") (pintype "passive"))
    )
    (net (code "20") (name "Net-(Q2-D)") (class "Default")
      (node (ref "D3") (pin "A") (pinfunction "A_A") (pintype "passive"))
      (node (ref "J11") (pin "2") (pinfunction "2_2") (pintype "passive"))
      (node (ref "Q2") (pin "3") (pinfunction "D_3") (pintype "passive"))
    )
    (net (code "21") (name "Net-(Q2-G)") (class "Default")
      (node (ref "Q2") (pin "1") (pinfunction "G_1") (pintype "passive"))
      (node (ref "R13") (pin "1") (pinfunction "1_1") (pintype "passive"))
      (node (ref "R14") (pin "2") (pinfunction "2_2") (pintype "passive"))
    )
    (net (code "22") (name "Net-(Q3-D)") (class "Default")
      (node (ref "D4") (pin "A") (pinfunction "A_A") (pintype "passive"))
      (node (ref "J12") (pin "2") (pinfunction "2_2") (pintype "passive"))
      (node (ref "Q3") (pin "3") (pinfunction "D_3") (pintype "passive"))
    )
    (net (code "23") (name "Net-(Q3-G)") (class "Default")
      (node (ref "Q3") (pin "1") (pinfunction "G_1") (pintype "passive"))
      (node (ref "R15") (pin "1") (pinfunction "1_1") (pintype "passive"))
      (node (ref "R16") (pin "2") (pinfunction "2_2") (pintype "passive"))
    )
    (net (code "24") (name "Net-(R5-Pad2)") (class "Default")
      (node (ref "R5") (pin "2") (pinfunction "2_2") (pintype "passive"))
      (node (ref "USERLED") (pin "A") (pinfunction "A_A") (pintype "passive"))
    )
    (net (code "25") (name "Net-(R18-Pad1)") (class "Default")
      (node (ref "R18") (pin "1") (pinfunction "1_1") (pintype "passive"))
      (node (ref "USB2") (pin "VBUS") (pinfunction "VBUS_VBUS") (pintype "bidirectional"))
    )
    (net (code "26") (name "Net-(U1-IO5)") (class "Default")
      (node (ref "J3") (pin "3") (pinfunction "3_3") (pintype "passive"))
      (node (ref "R5") (pin "1") (pinfunction "1_1") (pintype "passive"))
      (node (ref "U1") (pin "29") (pinfunction "IO5_29") (pintype "bidirectional"))
    )
    (net (code "27") (name "Net-(U1-IO19)") (class "Default")
      (node (ref "J3") (pin "1") (pinfunction "1_1") (pintype "passive"))
      (node (ref "U1") (pin "31") (pinfunction "IO19_31") (pintype "bidirectional"))
    )
    (net (code "28") (name "Net-(U1-IO25)") (class "Default")
      (node (ref "J2") (pin "2") (pinfunction "2_2") (pintype "passive"))
      (node (ref "U1") (pin "10") (pinfunction "IO25_10") (pintype "bidirectional"))
    )
    (net (code "29") (name "Net-(U1-IO26)") (class "Default")
      (node (ref "J2") (pin "1") (pinfunction "1_1") (pintype "passive"))
      (node (ref "U1") (pin "11") (pinfunction "IO26_11") (pintype "bidirectional"))
    )
    (net (code "30") (name "Net-(U1-IO32)") (class "Default")
      (node (ref "J2") (pin "4") (pinfunction "4_4") (pintype "passive"))
      (node (ref "U1") (pin "8") (pinfunction "IO32_8") (pintype "bidirectional"))
    )
    (net (code "31") (name "Net-(U1-IO33)") (class "Default")
      (node (ref "J2") (pin "3") (pinfunction "3_3") (pintype "passive"))
      (node (ref "U1") (pin "9") (pinfunction "IO33_9") (pintype "bidirectional"))
    )
    (net (code "32") (name "Net-(U1-IO34)") (class "Default")
      (node (ref "J1") (pin "2") (pinfunction "2_2") (pintype "passive"))
      (node (ref "U1") (pin "6") (pinfunction "IO34_6") (pintype "bidirectional"))
    )
    (net (code "33") (name "Net-(U1-IO35)") (class "Default")
      (node (ref "J1") (pin "1") (pinfunction "1_1") (pintype "passive"))
      (node (ref "U1") (pin "7") (pinfunction "IO35_7") (pintype "bidirectional"))
    )
    (net (code "34") (name "Net-(U1-SENSOR_VN)") (class "Default")
      (node (ref "J1") (pin "3") (pinfunction "3_3") (pintype "passive"))
      (node (ref "U1") (pin "5") (pinfunction "SENSOR_VN_5") (pintype "bidirectional"))
    )
    (net (code "35") (name "Net-(U1-SENSOR_VP)") (class "Default")
      (node (ref "J1") (pin "4") (pinfunction "4_4") (pintype "passive"))
      (node (ref "U1") (pin "4") (pinfunction "SENSOR_VP_4") (pintype "bidirectional"))
    )
    (net (code "36") (name "Net-(U2-D+)") (class "Default")
      (node (ref "U2") (pin "19") (pinfunction "D+_19") (pintype "bidirectional"))
      (node (ref "USB1") (pin "D+") (pinfunction "D+_D+") (pintype "bidirectional"))
    )
    (net (code "37") (name "Net-(U2-D-)") (class "Default")
      (node (ref "U2") (pin "18") (pinfunction "D-_18") (pintype "bidirectional"))
      (node (ref "USB1") (pin "D-") (pinfunction "D-_D-") (pintype "bidirectional"))
    )
    (net (code "38") (name "Net-(U2-OSC1)") (class "Default")
      (node (ref "C6") (pin "1") (pinfunction "1_1") (pintype "passive"))
      (node (ref "U2") (pin "2") (pinfunction "OSC1_2") (pintype "bidirectional"))
      (node (ref "Y1") (pin "P$2") (pinfunction "2_P$2") (pintype "passive"))
    )
    (net (code "39") (name "Net-(U2-OSC2)") (class "Default")
      (node (ref "C7") (pin "1") (pinfunction "1_1") (pintype "passive"))
      (node (ref "U2") (pin "3") (pinfunction "OSC2_3") (pintype "bidirectional"))
      (node (ref "Y1") (pin "P$1") (pinfunction "1_P$1") (pintype "passive"))
    )
    (net (code "40") (name "Net-(U2-RST)") (class "Default")
      (node (ref "R4") (pin "2") (pinfunction "2_2") (pintype "passive"))
      (node (ref "U2") (pin "4") (pinfunction "RST_4") (pintype "bidirectional"))
    )
    (net (code "41") (name "Net-(U4-PA00(XIN32{slash}SER1:0{slash}TC2:0))") (class "Default")
      (node (ref "J13") (pin "4") (pinfunction "4_4") (pintype "passive"))
      (node (ref "U4") (pin "1") (pinfunction "PA00(XIN32/SER1:0/TC2:0)_1") (pintype "bidirectional"))
    )
    (net (code "42") (name "Net-(U4-PA01(XOUT32{slash}SER1:1{slash}TC2:1))") (class "Default")
      (node (ref "J13") (pin "3") (pinfunction "3_3") (pintype "passive"))
      (node (ref "U4") (pin "2") (pinfunction "PA01(XOUT32/SER1:1/TC2:1)_2") (pintype "bidirectional"))
    )
    (net (code "43") (name "Net-(U4-PA02(AIN0{slash}DAC))") (class "Default")
      (node (ref "J13") (pin "1") (pinfunction "1_1") (pintype "passive"))
      (node (ref "U4") (pin "3") (pinfunction "PA02(AIN0/DAC)_3") (pintype "bidirectional"))
    )
    (net (code "44") (name "Net-(U4-PA03(AIN1{slash}REFA))") (class "Default")
      (node (ref "J13") (pin "2") (pinfunction "2_2") (pintype "passive"))
      (node (ref "U4") (pin "4") (pinfunction "PA03(AIN1/REFA)_4") (pintype "bidirectional"))
    )
    (net (code "45") (name "Net-(U4-PA14(XIN{slash}SER2:2+))") (class "Default")
      (node (ref "C14") (pin "1") (pinfunction "1_1") (pintype "passive"))
      (node (ref "U4") (pin "23") (pinfunction "PA14(XIN/SER2:2+)_23") (pintype "bidirectional"))
      (node (ref "Y2") (pin "P$2") (pinfunction "2_P$2") (pintype "passive"))
    )
    (net (code "46") (name "Net-(U4-PA15(XOUT{slash}SER2:3+))") (class "Default")
      (node (ref "C15") (pin "1") (pinfunction "1_1") (pintype "passive"))
      (node (ref "U4") (pin "24") (pinfunction "PA15(XOUT/SER2:3+)_24") (pintype "bidirectional"))
      (node (ref "Y2") (pin "P$1") (pinfunction "1_P$1") (pintype "passive"))
    )
    (net (code "47") (name "Net-(U4-PA24(SER3:2+))") (class "Default")
      (node (ref "U4") (pin "33") (pinfunction "PA24(SER3:2+)_33") (pintype "bidirectional"))
      (node (ref "USB2") (pin "D-") (pinfunction "D-_D-") (pintype "bidirectional"))
    )
    (net (code "48") (name "Net-(U4-PA25(SER3:3+))") (class "Default")
      (node (ref "U4") (pin "34") (pinfunction "PA25(SER3:3+)_34") (pintype "bidirectional"))
      (node (ref "USB2") (pin "D+") (pinfunction "D+_D+") (pintype "bidirectional"))
    )
    (net (code "49") (name "Net-(U4-PB03(AIN11{slash}SER5:1))") (class "Default")
      (node (ref "R19") (pin "1") (pinfunction "1_1") (pintype "passive"))
      (node (ref "U4") (pin "48") (pinfunction "PB03(AIN11/SER5:1)_48") (pintype "bidirectional"))
    )
    (net (code "50") (name "Net-(U4-VDDCORE)") (class "Default")
      (node (ref "C13") (pin "2") (pinfunction "2_2") (pintype "passive"))
      (node (ref "U4") (pin "43") (pinfunction "VDDCORE_43") (pintype "bidirectional"))
    )
    (net (code "51") (name "OE_AP") (class "Default")
      (node (ref "IC2") (pin "1") (pinfunction "OE_1") (pintype "input"))
      (node (ref "IC3") (pin "1") (pinfunction "OE_1") (pintype "input"))
      (node (ref "U2") (pin "7") (pinfunction "GP5_7") (pintype "bidirectional"))
    )
    (net (code "52") (name "PW1") (class "Default")
      (node (ref "R11") (pin "2") (pinfunction "2_2") (pintype "passive"))
      (node (ref "U1") (pin "37") (pinfunction "IO23_37") (pintype "bidirectional"))
    )
    (net (code "53") (name "PW2") (class "Default")
      (node (ref "R13") (pin "2") (pinfunction "2_2") (pintype "passive"))
      (node (ref "U1") (pin "36") (pinfunction "IO22_36") (pintype "bidirectional"))
    )
    (net (code "54") (name "PW3") (class "Default")
      (node (ref "R15") (pin "2") (pinfunction "2_2") (pintype "passive"))
      (node (ref "U1") (pin "33") (pinfunction "IO21_33") (pintype "bidirectional"))
    )
    (net (code "55") (name "P_AP") (class "Default")
      (node (ref "IC2") (pin "2") (pinfunction "I_2") (pintype "input"))
      (node (ref "U2") (pin "8") (pinfunction "GP4_8") (pintype "bidirectional"))
    )
    (net (code "56") (name "RX") (class "Default")
      (node (ref "U1") (pin "34") (pinfunction "RXD0_34") (pintype "bidirectional"))
      (node (ref "U2") (pin "10") (pinfunction "TX_10") (pintype "bidirectional"))
    )
    (net (code "57") (name "TX") (class "Default")
      (node (ref "U1") (pin "35") (pinfunction "TXD0_35") (pintype "bidirectional"))
      (node (ref "U2") (pin "12") (pinfunction "RX_12") (pintype "bidirectional"))
    )
    (net (code "58") (name "unconnected-(U1-CLK-Pad20)") (class "Default")
      (node (ref "U1") (pin "20") (pinfunction "CLK_20") (pintype "bidirectional"))
    )
    (net (code "59") (name "unconnected-(U1-CMD-Pad19)") (class "Default")
      (node (ref "U1") (pin "19") (pinfunction "CMD_19") (pintype "bidirectional"))
    )
    (net (code "60") (name "unconnected-(U1-NC-Pad32)") (class "Default")
      (node (ref "U1") (pin "32") (pinfunction "NC_32") (pintype "bidirectional"))
    )
    (net (code "61") (name "unconnected-(U1-SD1-Pad22)") (class "Default")
      (node (ref "U1") (pin "22") (pinfunction "SD1_22") (pintype "bidirectional"))
    )
    (net (code "62") (name "unconnected-(U1-SD2-Pad17)") (class "Default")
      (node (ref "U1") (pin "17") (pinfunction "SD2_17") (pintype "bidirectional"))
    )
    (net (code "63") (name "unconnected-(U1-SD3-Pad18)") (class "Default")
      (node (ref "U1") (pin "18") (pinfunction "SD3_18") (pintype "bidirectional"))
    )
    (net (code "64") (name "unconnected-(U1-SDO-Pad21)") (class "Default")
      (node (ref "U1") (pin "21") (pinfunction "SDO_21") (pintype "bidirectional"))
    )
    (net (code "65") (name "unconnected-(U2-CTS-Pad13)") (class "Default")
      (node (ref "U2") (pin "13") (pinfunction "CTS_13") (pintype "bidirectional"))
    )
    (net (code "66") (name "unconnected-(U2-GP0-Pad16)") (class "Default")
      (node (ref "U2") (pin "16") (pinfunction "GP0_16") (pintype "bidirectional"))
    )
    (net (code "67") (name "unconnected-(U2-GP1-Pad15)") (class "Default")
      (node (ref "U2") (pin "15") (pinfunction "GP1_15") (pintype "bidirectional"))
    )
    (net (code "68") (name "unconnected-(U2-GP2-Pad14)") (class "Default")
      (node (ref "U2") (pin "14") (pinfunction "GP2_14") (pintype "bidirectional"))
    )
    (net (code "69") (name "unconnected-(U2-GP6-Pad6)") (class "Default")
      (node (ref "U2") (pin "6") (pinfunction "GP6_6") (pintype "bidirectional"))
    )
    (net (code "70") (name "unconnected-(U2-GP7-Pad5)") (class "Default")
      (node (ref "U2") (pin "5") (pinfunction "GP7_5") (pintype "bidirectional"))
    )
    (net (code "71") (name "unconnected-(U2-RTS-Pad11)") (class "Default")
      (node (ref "U2") (pin "11") (pinfunction "RTS_11") (pintype "bidirectional"))
    )
    (net (code "72") (name "unconnected-(U3-CD-PadP$10)") (class "Default")
      (node (ref "U3") (pin "P$10") (pinfunction "CD_P$10") (pintype "bidirectional"))
    )
    (net (code "73") (name "unconnected-(U3-GND2-PadP$9)") (class "Default")
      (node (ref "U3") (pin "P$9") (pinfunction "GND2_P$9") (pintype "bidirectional"))
    )
    (net (code "74") (name "unconnected-(U4-PA04(AIN4{slash}REFB{slash}SER0:0{slash}TC0:0)-Pad9)") (class "Default")
      (node (ref "U4") (pin "9") (pinfunction "PA04(AIN4/REFB/SER0:0/TC0:0)_9") (pintype "bidirectional"))
    )
    (net (code "75") (name "unconnected-(U4-PA05(AIN5{slash}SER0:1{slash}TC0:1)-Pad10)") (class "Default")
      (node (ref "U4") (pin "10") (pinfunction "PA05(AIN5/SER0:1/TC0:1)_10") (pintype "bidirectional"))
    )
    (net (code "76") (name "unconnected-(U4-PA06(AIN6{slash}SER0:2{slash}TC1:0)-Pad11)") (class "Default")
      (node (ref "U4") (pin "11") (pinfunction "PA06(AIN6/SER0:2/TC1:0)_11") (pintype "bidirectional"))
    )
    (net (code "77") (name "unconnected-(U4-PA07(AIN7{slash}SER0:3{slash}TC1:1)-Pad12)") (class "Default")
      (node (ref "U4") (pin "12") (pinfunction "PA07(AIN7/SER0:3/TC1:1)_12") (pintype "bidirectional"))
    )
    (net (code "78") (name "unconnected-(U4-PA08(I2C{slash}AIN16{slash}SER0:0+)-Pad13)") (class "Default")
      (node (ref "U4") (pin "13") (pinfunction "PA08(I2C/AIN16/SER0:0+)_13") (pintype "bidirectional"))
    )
    (net (code "79") (name "unconnected-(U4-PA09(I2C{slash}AIN17{slash}SER0:1+)-Pad14)") (class "Default")
      (node (ref "U4") (pin "14") (pinfunction "PA09(I2C/AIN17/SER0:1+)_14") (pintype "bidirectional"))
    )
    (net (code "80") (name "unconnected-(U4-PA10(AIN18{slash}SER0:2+)-Pad15)") (class "Default")
      (node (ref "U4") (pin "15") (pinfunction "PA10(AIN18/SER0:2+)_15") (pintype "bidirectional"))
    )
    (net (code "81") (name "unconnected-(U4-PA11(AIN19{slash}SER0:3+)-Pad16)") (class "Default")
      (node (ref "U4") (pin "16") (pinfunction "PA11(AIN19/SER0:3+)_16") (pintype "bidirectional"))
    )
    (net (code "82") (name "unconnected-(U4-PA12(I2C{slash}SER2:0+)-Pad21)") (class "Default")
      (node (ref "U4") (pin "21") (pinfunction "PA12(I2C/SER2:0+)_21") (pintype "bidirectional"))
    )
    (net (code "83") (name "unconnected-(U4-PA13(I2C{slash}SER2:1+)-Pad22)") (class "Default")
      (node (ref "U4") (pin "22") (pinfunction "PA13(I2C/SER2:1+)_22") (pintype "bidirectional"))
    )
    (net (code "84") (name "unconnected-(U4-PA16(I2C{slash}SER1:0+)-Pad25)") (class "Default")
      (node (ref "U4") (pin "25") (pinfunction "PA16(I2C/SER1:0+)_25") (pintype "bidirectional"))
    )
    (net (code "85") (name "unconnected-(U4-PA17(I2C{slash}SER1:1+)-Pad26)") (class "Default")
      (node (ref "U4") (pin "26") (pinfunction "PA17(I2C/SER1:1+)_26") (pintype "bidirectional"))
    )
    (net (code "86") (name "unconnected-(U4-PA18(SER1:2+)-Pad27)") (class "Default")
      (node (ref "U4") (pin "27") (pinfunction "PA18(SER1:2+)_27") (pintype "bidirectional"))
    )
    (net (code "87") (name "unconnected-(U4-PA19(SER1:3+)-Pad28)") (class "Default")
      (node (ref "U4") (pin "28") (pinfunction "PA19(SER1:3+)_28") (pintype "bidirectional"))
    )
    (net (code "88") (name "unconnected-(U4-PA20(SER5:2+)-Pad29)") (class "Default")
      (node (ref "U4") (pin "29") (pinfunction "PA20(SER5:2+)_29") (pintype "bidirectional"))
    )
    (net (code "89") (name "unconnected-(U4-PA21(SER5:3+)-Pad30)") (class "Default")
      (node (ref "U4") (pin "30") (pinfunction "PA21(SER5:3+)_30") (pintype "bidirectional"))
    )
    (net (code "90") (name "unconnected-(U4-PA22(I2C{slash}SER3:0+)-Pad31)") (class "Default")
      (node (ref "U4") (pin "31") (pinfunction "PA22(I2C/SER3:0+)_31") (pintype "bidirectional"))
    )
    (net (code "91") (name "unconnected-(U4-PA23(I2C{slash}SER3:0+)-Pad32)") (class "Default")
      (node (ref "U4") (pin "32") (pinfunction "PA23(I2C/SER3:0+)_32") (pintype "bidirectional"))
    )
    (net (code "92") (name "unconnected-(U4-PA28-Pad41)") (class "Default")
      (node (ref "U4") (pin "41") (pinfunction "PA28_41") (pintype "bidirectional"))
    )
    (net (code "93") (name "unconnected-(U4-PB02(AIN10{slash}SER5:0)-Pad47)") (class "Default")
      (node (ref "U4") (pin "47") (pinfunction "PB02(AIN10/SER5:0)_47") (pintype "bidirectional"))
    )
    (net (code "94") (name "unconnected-(U4-PB08(AIN2{slash}SER4:0{slash}TC4:0)-Pad7)") (class "Default")
      (node (ref "U4") (pin "7") (pinfunction "PB08(AIN2/SER4:0/TC4:0)_7") (pintype "bidirectional"))
    )
    (net (code "95") (name "unconnected-(U4-PB09(AIN3{slash}SER4:1{slash}TC4:1)-Pad8)") (class "Default")
      (node (ref "U4") (pin "8") (pinfunction "PB09(AIN3/SER4:1/TC4:1)_8") (pintype "bidirectional"))
    )
    (net (code "96") (name "unconnected-(U4-PB10(SER4:2+)-Pad19)") (class "Default")
      (node (ref "U4") (pin "19") (pinfunction "PB10(SER4:2+)_19") (pintype "bidirectional"))
    )
    (net (code "97") (name "unconnected-(U4-PB11(SER4:3+)-Pad20)") (class "Default")
      (node (ref "U4") (pin "20") (pinfunction "PB11(SER4:3+)_20") (pintype "bidirectional"))
    )
    (net (code "98") (name "unconnected-(U4-PB22(SER5:2+)-Pad37)") (class "Default")
      (node (ref "U4") (pin "37") (pinfunction "PB22(SER5:2+)_37") (pintype "bidirectional"))
    )
    (net (code "99") (name "unconnected-(U4-PB23(SER5:3+)-Pad38)") (class "Default")
      (node (ref "U4") (pin "38") (pinfunction "PB23(SER5:3+)_38") (pintype "bidirectional"))
    )
    (net (code "100") (name "unconnected-(USB1-PadID)") (class "Default")
      (node (ref "USB1") (pin "ID") (pinfunction "ID_ID") (pintype "bidirectional"))
    )
    (net (code "101") (name "unconnected-(USB2-PadID)") (class "Default")
      (node (ref "USB2") (pin "ID") (pinfunction "ID_ID") (pintype "bidirectional"))
    )
  )
)
